# lighting.net
KiCad netlist of a schematic drawn in EAGLE
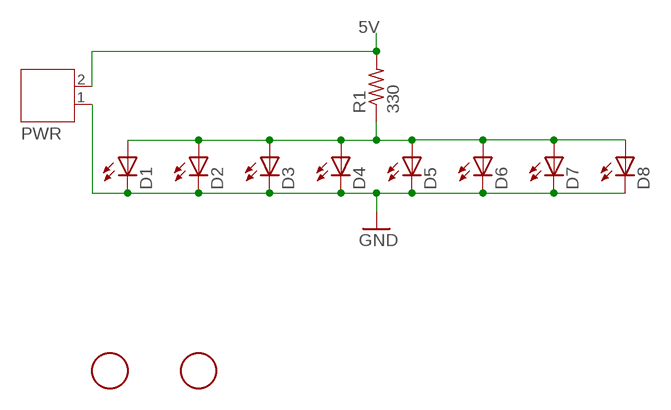
[diagram p0: schematic, sheet 1]

(export (version "E")
  (design (tool "Eeschema 10.0.6"))
  (components
    (comp (ref "D1")
      (value "LEDCHIPLED_1206")
      (footprint "eagle-import:CHIPLED_1206")
      (libsource (lib "eagle-import") (part "LEDCHIPLED_1206"))
    )
    (comp (ref "D2")
      (value "LEDCHIPLED_1206")
      (footprint "eagle-import:CHIPLED_1206")
      (libsource (lib "eagle-import") (part "LEDCHIPLED_1206"))
    )
    (comp (ref "D3")
      (value "LEDCHIPLED_1206")
      (footprint "eagle-import:CHIPLED_1206")
      (libsource (lib "eagle-import") (part "LEDCHIPLED_1206"))
    )
    (comp (ref "D4")
      (value "LEDCHIPLED_1206")
      (footprint "eagle-import:CHIPLED_1206")
      (libsource (lib "eagle-import") (part "LEDCHIPLED_1206"))
    )
    (comp (ref "D5")
      (value "LEDCHIPLED_1206")
      (footprint "eagle-import:CHIPLED_1206")
      (libsource (lib "eagle-import") (part "LEDCHIPLED_1206"))
    )
    (comp (ref "D6")
      (value "LEDCHIPLED_1206")
      (footprint "eagle-import:CHIPLED_1206")
      (libsource (lib "eagle-import") (part "LEDCHIPLED_1206"))
    )
    (comp (ref "D7")
      (value "LEDCHIPLED_1206")
      (footprint "eagle-import:CHIPLED_1206")
      (libsource (lib "eagle-import") (part "LEDCHIPLED_1206"))
    )
    (comp (ref "D8")
      (value "LEDCHIPLED_1206")
      (footprint "eagle-import:CHIPLED_1206")
      (libsource (lib "eagle-import") (part "LEDCHIPLED_1206"))
    )
    (comp (ref "PWR")
      (value "JST-PH2")
      (footprint "eagle-import:JST-PH2")
      (libsource (lib "eagle-import") (part "JST-PH2"))
    )
    (comp (ref "R1")
      (value "330")
      (footprint "eagle-import:R1206")
      (libsource (lib "eagle-import") (part "R-US_R1206"))
    )
    (comp (ref "U$1")
      (value "FIDUCIAL")
      (footprint "eagle-import:FIDUCIAL_1MM")
      (libsource (lib "eagle-import") (part "FIDUCIAL"))
    )
    (comp (ref "U$2")
      (value "FIDUCIAL")
      (footprint "eagle-import:FIDUCIAL_1MM")
      (libsource (lib "eagle-import") (part "FIDUCIAL"))
    )
  )
  (nets
    (net (code "1") (name "/5V") (class "Default")
      (node (ref "PWR") (pin "2") (pinfunction "2_2") (pintype "passive"))
      (node (ref "R1") (pin "2") (pinfunction "2_2") (pintype "passive"))
    )
    (net (code "2") (name "GND") (class "Default")
      (node (ref "D1") (pin "C") (pinfunction "C_C") (pintype "passive"))
      (node (ref "D2") (pin "C") (pinfunction "C_C") (pintype "passive"))
      (node (ref "D3") (pin "C") (pinfunction "C_C") (pintype "passive"))
      (node (ref "D4") (pin "C") (pinfunction "C_C") (pintype "passive"))
      (node (ref "D5") (pin "C") (pinfunction "C_C") (pintype "passive"))
      (node (ref "D6") (pin "C") (pinfunction "C_C") (pintype "passive"))
      (node (ref "D7") (pin "C") (pinfunction "C_C") (pintype "passive"))
      (node (ref "D8") (pin "C") (pinfunction "C_C") (pintype "passive"))
      (node (ref "PWR") (pin "1") (pinfunction "1_1") (pintype "passive"))
    )
    (net (code "3") (name "Net-(D1-PadA)") (class "Default")
      (node (ref "D1") (pin "A") (pinfunction "A_A") (pintype "passive"))
      (node (ref "D2") (pin "A") (pinfunction "A_A") (pintype "passive"))
      (node (ref "D3") (pin "A") (pinfunction "A_A") (pintype "passive"))
      (node (ref "D4") (pin "A") (pinfunction "A_A") (pintype "passive"))
      (node (ref "D5") (pin "A") (pinfunction "A_A") (pintype "passive"))
      (node (ref "D6") (pin "A") (pinfunction "A_A") (pintype "passive"))
      (node (ref "D7") (pin "A") (pinfunction "A_A") (pintype "passive"))
      (node (ref "D8") (pin "A") (pinfunction "A_A") (pintype "passive"))
      (node (ref "R1") (pin "1") (pinfunction "1_1") (pintype "passive"))
    )
  )
)
